# design.net
KiCad netlist of a schematic drawn in Altium Designer
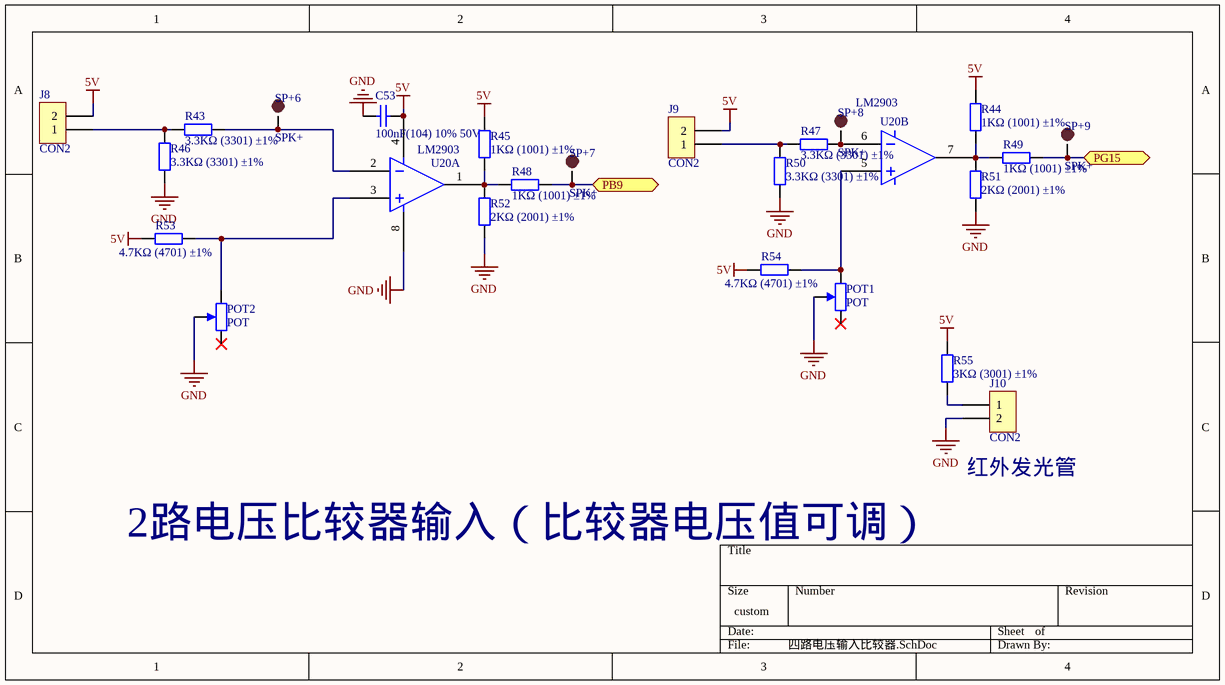
[diagram p0: 四路电压输入比较器.SchDoc]

(export (version "E")
  (design (tool "Eeschema 10.0.6"))
  (components
    (comp (ref "C53")
      (value "100nF(104) 10% 50V")
      (footprint "0805_C")
      (description "贴片电容")
      (libsource (lib "Cap") (part "0805 100nF(104) 10% 50V"))
    )
    (comp (ref "J8")
      (value "CON2")
      (footprint "Connector:XH2.54-2P")
      (description "连接器")
      (libsource (lib "") (part "CON2_1"))
    )
    (comp (ref "J9")
      (value "CON2")
      (footprint "Connector:XH2.54-2P")
      (description "连接器")
      (libsource (lib "") (part "CON2_1"))
    )
    (comp (ref "J10")
      (value "CON2")
      (footprint "Connector:XH2.54-2P")
      (description "连接器")
      (libsource (lib "Connector") (part "CON2"))
    )
    (comp (ref "POT1")
      (value "POT")
      (footprint "R09-5K")
      (description "Potentiometer")
      (libsource (lib "淘宝封装") (part "POT"))
    )
    (comp (ref "POT2")
      (value "POT")
      (footprint "R09-5K")
      (description "Potentiometer")
      (libsource (lib "淘宝封装") (part "POT"))
    )
    (comp (ref "R43")
      (value "3.3KΩ (3301) ±1%")
      (footprint "0805_R")
      (description "贴片电阻")
      (libsource (lib "RES") (part "0805 3.3KΩ (3301) 1%"))
    )
    (comp (ref "R44")
      (value "1KΩ (1001) ±1%")
      (footprint "0805_R")
      (description "贴片电阻")
      (libsource (lib "RES") (part "0805 1KΩ (1001) 1%"))
    )
    (comp (ref "R45")
      (value "1KΩ (1001) ±1%")
      (footprint "0805_R")
      (description "贴片电阻")
      (libsource (lib "RES") (part "0805 1KΩ (1001) 1%"))
    )
    (comp (ref "R46")
      (value "3.3KΩ (3301) ±1%")
      (footprint "0805_R")
      (description "贴片电阻")
      (libsource (lib "") (part "0805 3.3KΩ (3301) 1%_1"))
    )
    (comp (ref "R47")
      (value "3.3KΩ (3301) ±1%")
      (footprint "0805_R")
      (description "贴片电阻")
      (libsource (lib "RES") (part "0805 3.3KΩ (3301) 1%"))
    )
    (comp (ref "R48")
      (value "1KΩ (1001) ±1%")
      (footprint "0805_R")
      (description "贴片电阻")
      (libsource (lib "") (part "0805 1KΩ (1001) 1%_1"))
    )
    (comp (ref "R49")
      (value "1KΩ (1001) ±1%")
      (footprint "0805_R")
      (description "贴片电阻")
      (libsource (lib "") (part "0805 1KΩ (1001) 1%_1"))
    )
    (comp (ref "R50")
      (value "3.3KΩ (3301) ±1%")
      (footprint "0805_R")
      (description "贴片电阻")
      (libsource (lib "") (part "0805 3.3KΩ (3301) 1%_1"))
    )
    (comp (ref "R51")
      (value "2KΩ (2001) ±1%")
      (footprint "0805_R")
      (description "贴片电阻")
      (libsource (lib "RES") (part "0805 2KΩ (2001) 1%"))
    )
    (comp (ref "R52")
      (value "2KΩ (2001) ±1%")
      (footprint "0805_R")
      (description "贴片电阻")
      (libsource (lib "RES") (part "0805 2KΩ (2001) 1%"))
    )
    (comp (ref "R53")
      (value "4.7KΩ (4701) ±1%")
      (footprint "0805_R")
      (description "贴片电阻")
      (libsource (lib "RES") (part "0805 4.7KΩ (4701) 1%"))
    )
    (comp (ref "R54")
      (value "4.7KΩ (4701) ±1%")
      (footprint "0805_R")
      (description "贴片电阻")
      (libsource (lib "RES") (part "0805 4.7KΩ (4701) 1%"))
    )
    (comp (ref "R55")
      (value "3KΩ (3001) ±1%")
      (footprint "0805_R")
      (description "贴片电阻")
      (libsource (lib "RES") (part "0805 3KΩ (3001) 1%"))
    )
    (comp (ref "SP+6")
      (value "SPK+")
      (footprint "TP-1.5")
      (description "测试点")
      (libsource (lib "EXPLORER") (part "TEST-POINT"))
    )
    (comp (ref "SP+7")
      (value "SPK+")
      (footprint "TP-1.5")
      (description "测试点")
      (libsource (lib "EXPLORER") (part "TEST-POINT"))
    )
    (comp (ref "SP+8")
      (value "SPK+")
      (footprint "TP-1.5")
      (description "测试点")
      (libsource (lib "EXPLORER") (part "TEST-POINT"))
    )
    (comp (ref "SP+9")
      (value "SPK+")
      (footprint "TP-1.5")
      (description "测试点")
      (libsource (lib "EXPLORER") (part "TEST-POINT"))
    )
    (comp (ref "U20") (value "LM2903") (footprint "SOP-8") (libsource (lib "*") (part "LM193")))
  )
  (nets
    (net (code "1") (name "/PB9") (class "Default")
      (node (ref "R48") (pin "1") (pinfunction "1_1") (pintype "passive"))
      (node (ref "SP+7") (pin "1") (pinfunction "1_1") (pintype "passive"))
    )
    (net (code "2") (name "/PG15") (class "Default")
      (node (ref "R49") (pin "1") (pinfunction "1_1") (pintype "passive"))
      (node (ref "SP+9") (pin "1") (pinfunction "1_1") (pintype "passive"))
    )
    (net (code "3") (name "5V") (class "Default")
      (node (ref "C53") (pin "1") (pinfunction "1_1") (pintype "passive"))
      (node (ref "J8") (pin "2") (pinfunction "2_2") (pintype "passive"))
      (node (ref "J9") (pin "2") (pinfunction "2_2") (pintype "passive"))
      (node (ref "R44") (pin "2") (pinfunction "2_2") (pintype "passive"))
      (node (ref "R45") (pin "2") (pinfunction "2_2") (pintype "passive"))
      (node (ref "R53") (pin "1") (pinfunction "1_1") (pintype "passive"))
      (node (ref "R54") (pin "1") (pinfunction "1_1") (pintype "passive"))
      (node (ref "R55") (pin "2") (pinfunction "2_2") (pintype "passive"))
      (node (ref "U20") (pin "4") (pintype "passive"))
    )
    (net (code "4") (name "GND") (class "Default")
      (node (ref "C53") (pin "2") (pinfunction "2_2") (pintype "passive"))
      (node (ref "J10") (pin "2") (pinfunction "2_2") (pintype "passive"))
      (node (ref "POT1") (pin "2") (pinfunction "2_2") (pintype "passive"))
      (node (ref "POT2") (pin "2") (pinfunction "2_2") (pintype "passive"))
      (node (ref "R46") (pin "1") (pinfunction "1_1") (pintype "passive"))
      (node (ref "R50") (pin "1") (pinfunction "1_1") (pintype "passive"))
      (node (ref "R51") (pin "1") (pinfunction "1_1") (pintype "passive"))
      (node (ref "R52") (pin "1") (pinfunction "1_1") (pintype "passive"))
      (node (ref "U20") (pin "8") (pintype "passive"))
    )
    (net (code "5") (name "Net-(J8-Pad1)") (class "Default")
      (node (ref "J8") (pin "1") (pinfunction "1_1") (pintype "passive"))
      (node (ref "R43") (pin "2") (pinfunction "2_2") (pintype "passive"))
      (node (ref "R46") (pin "2") (pinfunction "2_2") (pintype "passive"))
    )
    (net (code "6") (name "Net-(J9-Pad1)") (class "Default")
      (node (ref "J9") (pin "1") (pinfunction "1_1") (pintype "passive"))
      (node (ref "R47") (pin "2") (pinfunction "2_2") (pintype "passive"))
      (node (ref "R50") (pin "2") (pinfunction "2_2") (pintype "passive"))
    )
    (net (code "7") (name "Net-(J10-Pad1)") (class "Default")
      (node (ref "J10") (pin "1") (pinfunction "1_1") (pintype "passive"))
      (node (ref "R55") (pin "1") (pinfunction "1_1") (pintype "passive"))
    )
    (net (code "8") (name "Net-(POT1-Pad3)") (class "Default")
      (node (ref "POT1") (pin "3") (pinfunction "3_3") (pintype "passive"))
      (node (ref "R54") (pin "2") (pinfunction "2_2") (pintype "passive"))
      (node (ref "U20") (pin "5") (pintype "passive"))
    )
    (net (code "9") (name "Net-(POT2-Pad3)") (class "Default")
      (node (ref "POT2") (pin "3") (pinfunction "3_3") (pintype "passive"))
      (node (ref "R53") (pin "2") (pinfunction "2_2") (pintype "passive"))
      (node (ref "U20") (pin "3") (pintype "passive"))
    )
    (net (code "10") (name "Net-(R43-Pad1)") (class "Default")
      (node (ref "R43") (pin "1") (pinfunction "1_1") (pintype "passive"))
      (node (ref "SP+6") (pin "1") (pinfunction "1_1") (pintype "passive"))
      (node (ref "U20") (pin "2") (pintype "passive"))
    )
    (net (code "11") (name "Net-(R44-Pad1)") (class "Default")
      (node (ref "R44") (pin "1") (pinfunction "1_1") (pintype "passive"))
      (node (ref "R49") (pin "2") (pinfunction "2_2") (pintype "passive"))
      (node (ref "R51") (pin "2") (pinfunction "2_2") (pintype "passive"))
      (node (ref "U20") (pin "7") (pintype "passive"))
    )
    (net (code "12") (name "Net-(R45-Pad1)") (class "Default")
      (node (ref "R45") (pin "1") (pinfunction "1_1") (pintype "passive"))
      (node (ref "R48") (pin "2") (pinfunction "2_2") (pintype "passive"))
      (node (ref "R52") (pin "2") (pinfunction "2_2") (pintype "passive"))
      (node (ref "U20") (pin "1") (pintype "passive"))
    )
    (net (code "13") (name "Net-(R47-Pad1)") (class "Default")
      (node (ref "R47") (pin "1") (pinfunction "1_1") (pintype "passive"))
      (node (ref "SP+8") (pin "1") (pinfunction "1_1") (pintype "passive"))
      (node (ref "U20") (pin "6") (pintype "passive"))
    )
    (net (code "14") (name "unconnected-(POT1-Pad1)") (class "Default")
      (node (ref "POT1") (pin "1") (pinfunction "1_1") (pintype "passive+no_connect"))
    )
    (net (code "15") (name "unconnected-(POT2-Pad1)") (class "Default")
      (node (ref "POT2") (pin "1") (pinfunction "1_1") (pintype "passive+no_connect"))
    )
  )
)
